# MOSFET-Power-Control-v10.net
KiCad netlist of a schematic drawn in EAGLE
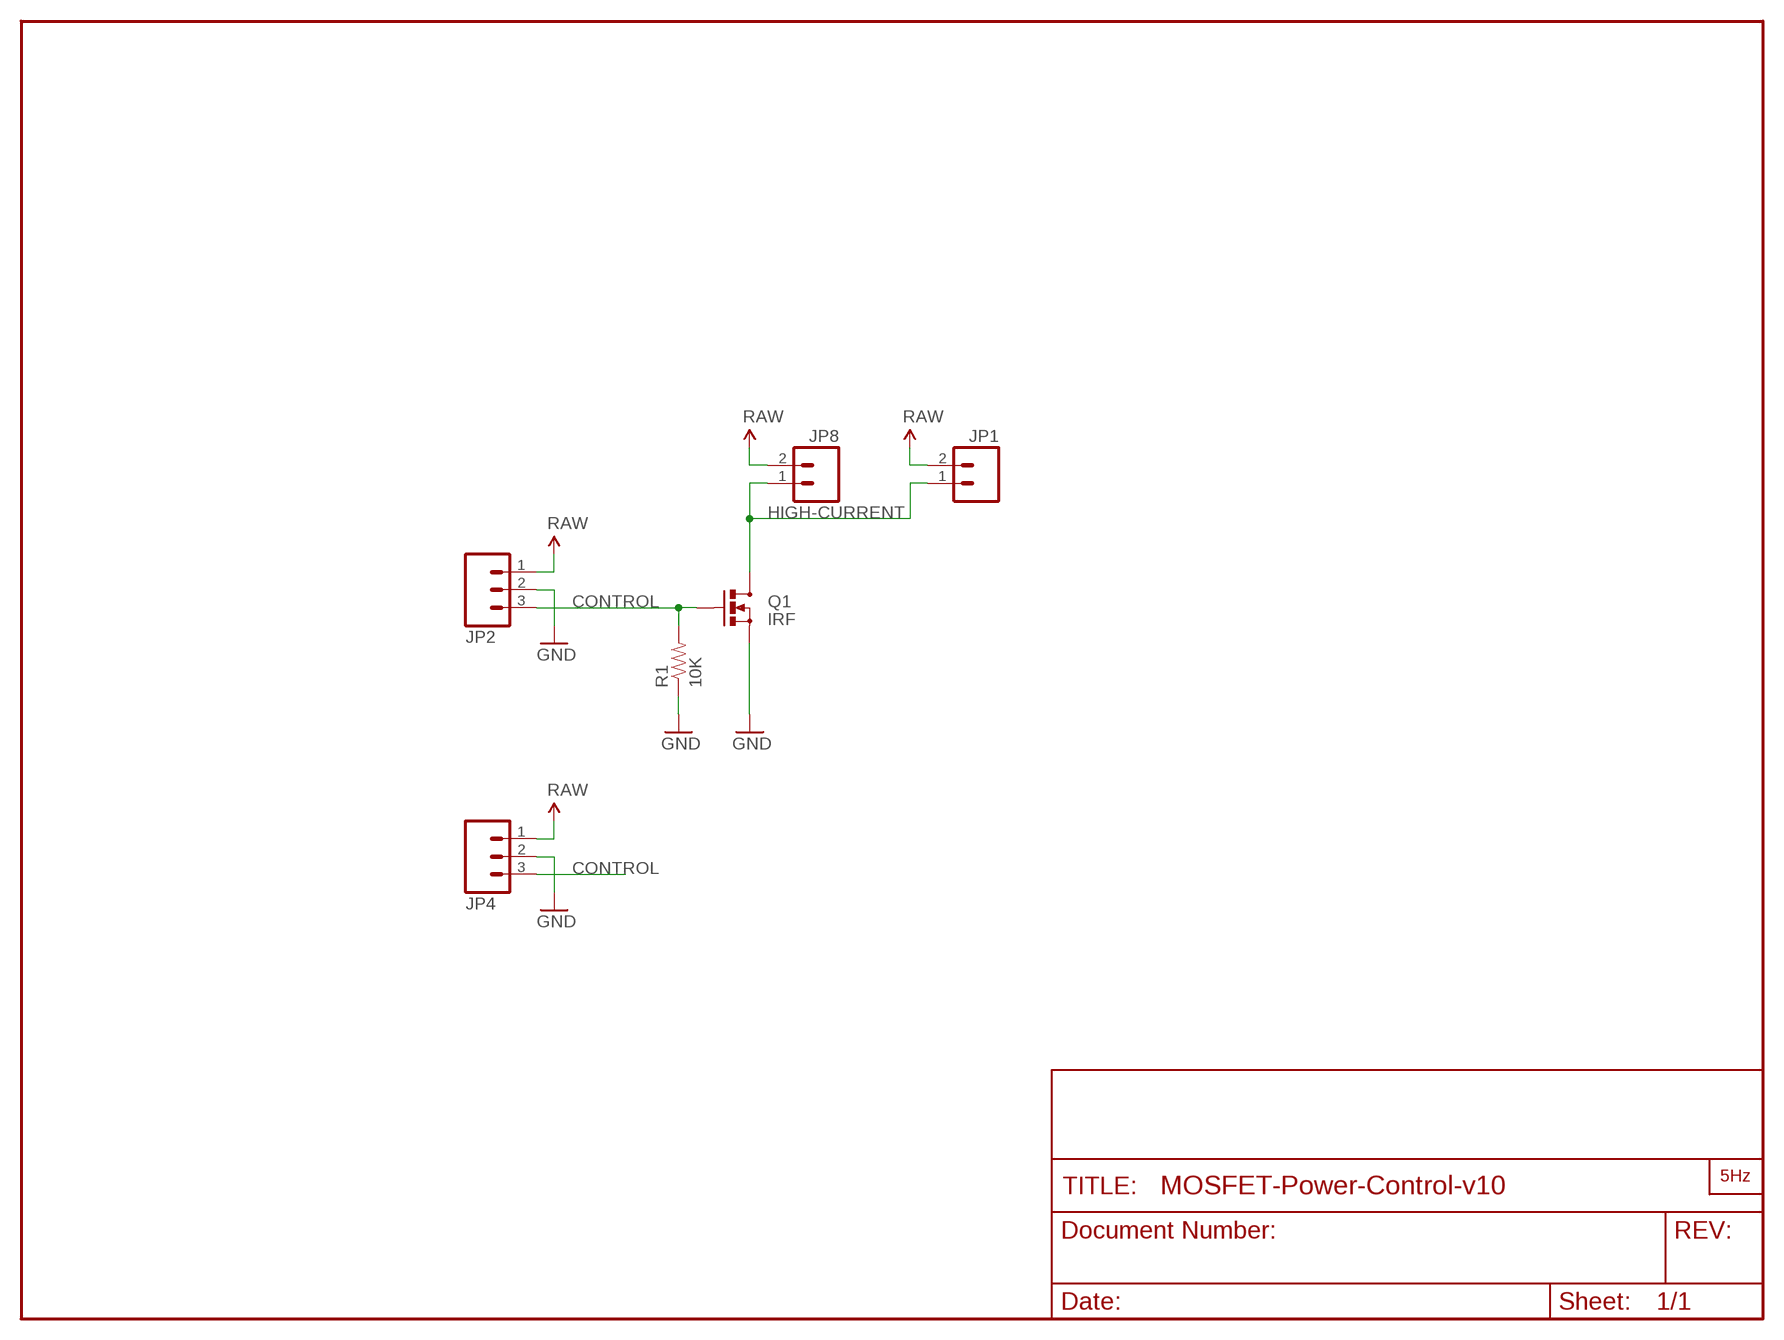
[diagram p0: schematic, sheet 1]

(export (version "E")
  (design (tool "Eeschema 10.0.6"))
  (components
    (comp (ref "JP1")
      (value "M023.5MM")
      (footprint "eagle-import:SCREWTERMINAL-3.5MM-2")
      (libsource (lib "eagle-import") (part "M023.5MM"))
    )
    (comp (ref "JP2")
      (value "M03JST-PTH")
      (footprint "eagle-import:JST-3-PTH")
      (libsource (lib "eagle-import") (part "M03JST-PTH"))
    )
    (comp (ref "JP4")
      (value "M03SCREW")
      (footprint "eagle-import:SCREWTERMINAL-3.5MM-3")
      (libsource (lib "eagle-import") (part "M03SCREW"))
    )
    (comp (ref "JP8")
      (value "M02JST-PTH-2")
      (footprint "eagle-import:JST-2-PTH")
      (libsource (lib "eagle-import") (part "M02JST-PTH-2"))
    )
    (comp (ref "Q1")
      (value "IRF")
      (footprint "eagle-import:TO220V")
      (libsource (lib "eagle-import") (part "MOSFET-NCHANNELPTH2"))
    )
    (comp (ref "R1")
      (value "10K")
      (footprint "eagle-import:AXIAL-0.3")
      (libsource (lib "eagle-import") (part "RESISTORPTH1"))
    )
    (comp (ref "U$1")
      (value "LOGO2_SILK5MM")
      (footprint "eagle-import:LOGO2_5MM")
      (libsource (lib "eagle-import") (part "LOGO2_SILK5MM"))
    )
  )
  (nets
    (net (code "1") (name "/CONTROL") (class "Default")
      (node (ref "JP2") (pin "3") (pinfunction "3_3") (pintype "passive"))
      (node (ref "JP4") (pin "3") (pinfunction "3_3") (pintype "passive"))
      (node (ref "Q1") (pin "1") (pinfunction "G_1") (pintype "passive"))
      (node (ref "R1") (pin "P$2") (pinfunction "2_P$2") (pintype "passive"))
    )
    (net (code "2") (name "/HIGH-CURRENT") (class "Default")
      (node (ref "JP1") (pin "1") (pinfunction "1_1") (pintype "passive"))
      (node (ref "JP8") (pin "1") (pinfunction "1_1") (pintype "passive"))
      (node (ref "Q1") (pin "2") (pinfunction "D_2") (pintype "passive"))
    )
    (net (code "3") (name "GND") (class "Default")
      (node (ref "JP2") (pin "2") (pinfunction "2_2") (pintype "passive"))
      (node (ref "JP4") (pin "2") (pinfunction "2_2") (pintype "passive"))
      (node (ref "Q1") (pin "3") (pinfunction "S_3") (pintype "passive"))
      (node (ref "R1") (pin "P$1") (pinfunction "1_P$1") (pintype "passive"))
    )
    (net (code "4") (name "RAW") (class "Default")
      (node (ref "JP1") (pin "2") (pinfunction "2_2") (pintype "passive"))
      (node (ref "JP2") (pin "1") (pinfunction "1_1") (pintype "passive"))
      (node (ref "JP4") (pin "1") (pinfunction "1_1") (pintype "passive"))
      (node (ref "JP8") (pin "2") (pinfunction "2_2") (pintype "passive"))
    )
  )
)
